# accelerometer_board.net
KiCad netlist of a schematic drawn in EAGLE
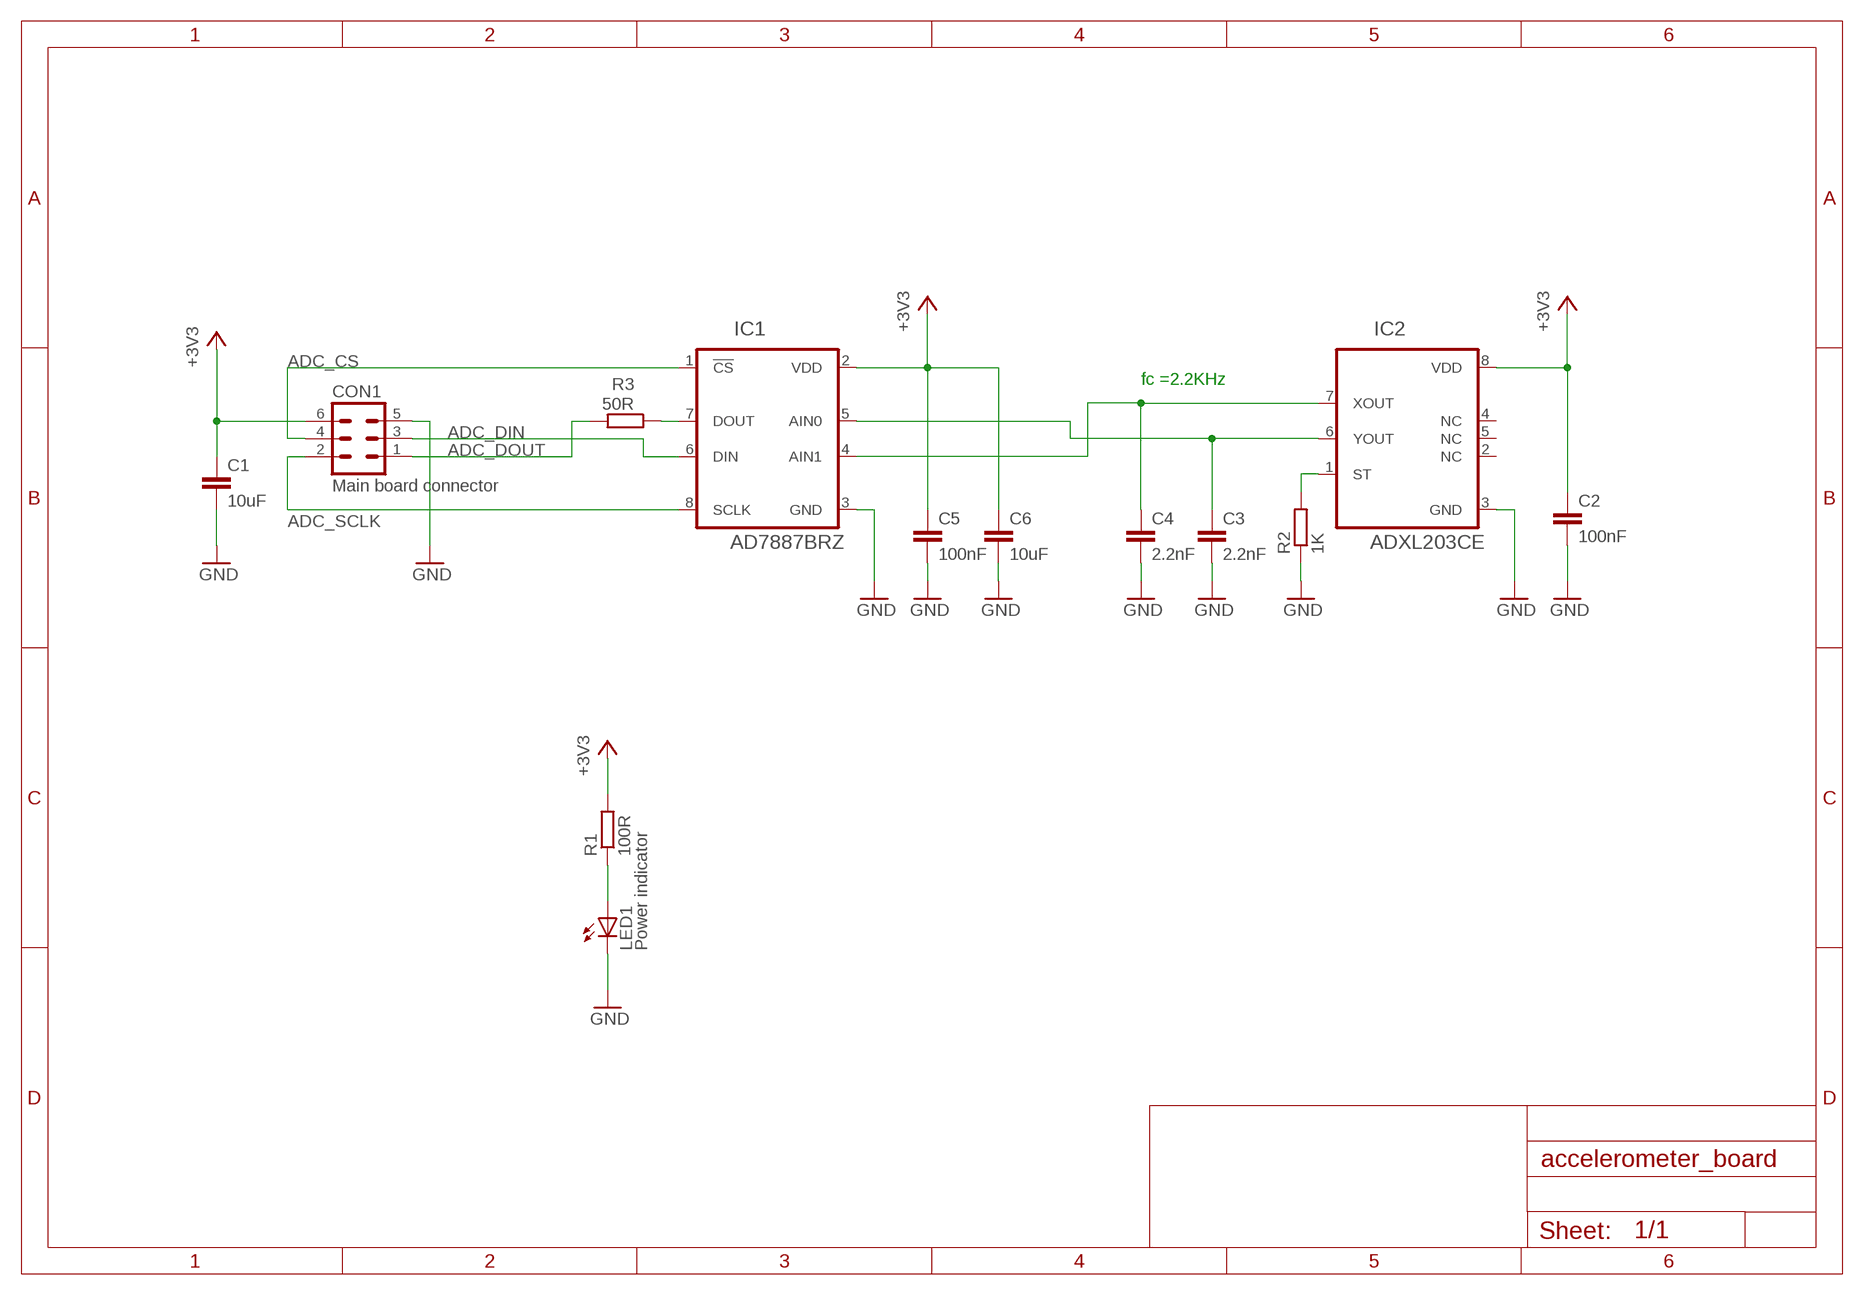
[diagram p0: schematic, sheet 1]

(export (version "E")
  (design (tool "Eeschema 10.0.6"))
  (components
    (comp (ref "C1")
      (value "10uF")
      (footprint "eagle-import:C1206K")
      (libsource (lib "eagle-import") (part "C-EUC1206K"))
    )
    (comp (ref "C2")
      (value "100nF")
      (footprint "eagle-import:C0805K")
      (libsource (lib "eagle-import") (part "C-EUC0805K"))
    )
    (comp (ref "C3")
      (value "2.2nF")
      (footprint "eagle-import:C0805K")
      (libsource (lib "eagle-import") (part "C-EUC0805K"))
    )
    (comp (ref "C4")
      (value "2.2nF")
      (footprint "eagle-import:C0805K")
      (libsource (lib "eagle-import") (part "C-EUC0805K"))
    )
    (comp (ref "C5")
      (value "100nF")
      (footprint "eagle-import:C0805K")
      (libsource (lib "eagle-import") (part "C-EUC0805K"))
    )
    (comp (ref "C6")
      (value "10uF")
      (footprint "eagle-import:C1206K")
      (libsource (lib "eagle-import") (part "C-EUC1206K"))
    )
    (comp (ref "CON1")
      (value "Main board connector")
      (footprint "eagle-import:ML6")
      (libsource (lib "eagle-import") (part "ML6"))
    )
    (comp (ref "IC1")
      (value "AD7887BRZ")
      (footprint "eagle-import:SO08")
      (libsource (lib "eagle-import") (part "AD7887BRZ"))
    )
    (comp (ref "IC2")
      (value "ADXL203CE")
      (footprint "eagle-import:LCC127P500X500X220-8N")
      (fields (field (name "MF") "Analog Devices") (field (name "MP") "ADXL203CE-REEL"))
      (libsource (lib "eagle-import") (part "ADXL203CE"))
    )
    (comp (ref "LED1")
      (value "Power indicator")
      (footprint "eagle-import:CHIP-LED0805")
      (libsource (lib "eagle-import") (part "LEDCHIP-LED0805"))
    )
    (comp (ref "R1")
      (value "100R")
      (footprint "eagle-import:R0805")
      (libsource (lib "eagle-import") (part "R-EU_R0805"))
    )
    (comp (ref "R2")
      (value "1K")
      (footprint "eagle-import:R0805")
      (libsource (lib "eagle-import") (part "R-EU_R0805"))
    )
    (comp (ref "R3")
      (value "50R")
      (footprint "eagle-import:R0805")
      (libsource (lib "eagle-import") (part "R-EU_R0805"))
    )
  )
  (nets
    (net (code "1") (name "+3V3") (class "Default")
      (node (ref "C1") (pin "1") (pinfunction "1_1") (pintype "passive"))
      (node (ref "C2") (pin "1") (pinfunction "1_1") (pintype "passive"))
      (node (ref "C5") (pin "1") (pinfunction "1_1") (pintype "passive"))
      (node (ref "C6") (pin "1") (pinfunction "1_1") (pintype "passive"))
      (node (ref "CON1") (pin "6") (pinfunction "6_6") (pintype "passive"))
      (node (ref "IC1") (pin "2") (pinfunction "VDD_2") (pintype "power_in"))
      (node (ref "IC2") (pin "8") (pinfunction "VDD_8") (pintype "power_in"))
      (node (ref "R1") (pin "2") (pinfunction "2_2") (pintype "passive"))
    )
    (net (code "2") (name "/ADC_CS") (class "Default")
      (node (ref "CON1") (pin "4") (pinfunction "4_4") (pintype "passive"))
      (node (ref "IC1") (pin "1") (pinfunction "~{CS}_1") (pintype "bidirectional"))
    )
    (net (code "3") (name "/ADC_DIN") (class "Default")
      (node (ref "CON1") (pin "3") (pinfunction "3_3") (pintype "passive"))
      (node (ref "IC1") (pin "6") (pinfunction "DIN_6") (pintype "input"))
    )
    (net (code "4") (name "/ADC_DOUT") (class "Default")
      (node (ref "CON1") (pin "1") (pinfunction "1_1") (pintype "passive"))
      (node (ref "R3") (pin "2") (pinfunction "2_2") (pintype "passive"))
    )
    (net (code "5") (name "/ADC_SCLK") (class "Default")
      (node (ref "CON1") (pin "2") (pinfunction "2_2") (pintype "passive"))
      (node (ref "IC1") (pin "8") (pinfunction "SCLK_8") (pintype "input"))
    )
    (net (code "6") (name "GND") (class "Default")
      (node (ref "C1") (pin "2") (pinfunction "2_2") (pintype "passive"))
      (node (ref "C2") (pin "2") (pinfunction "2_2") (pintype "passive"))
      (node (ref "C3") (pin "2") (pinfunction "2_2") (pintype "passive"))
      (node (ref "C4") (pin "2") (pinfunction "2_2") (pintype "passive"))
      (node (ref "C5") (pin "2") (pinfunction "2_2") (pintype "passive"))
      (node (ref "C6") (pin "2") (pinfunction "2_2") (pintype "passive"))
      (node (ref "CON1") (pin "5") (pinfunction "5_5") (pintype "passive"))
      (node (ref "IC1") (pin "3") (pinfunction "GND_3") (pintype "power_in"))
      (node (ref "IC2") (pin "3") (pinfunction "GND_3") (pintype "power_in"))
      (node (ref "LED1") (pin "C") (pinfunction "C_C") (pintype "passive"))
      (node (ref "R2") (pin "1") (pinfunction "1_1") (pintype "passive"))
    )
    (net (code "7") (name "Net-(IC1-AIN0)") (class "Default")
      (node (ref "C3") (pin "1") (pinfunction "1_1") (pintype "passive"))
      (node (ref "IC1") (pin "5") (pinfunction "AIN0_5") (pintype "input"))
      (node (ref "IC2") (pin "6") (pinfunction "YOUT_6") (pintype "output"))
    )
    (net (code "8") (name "Net-(IC1-AIN1)") (class "Default")
      (node (ref "C4") (pin "1") (pinfunction "1_1") (pintype "passive"))
      (node (ref "IC1") (pin "4") (pinfunction "AIN1_4") (pintype "input"))
      (node (ref "IC2") (pin "7") (pinfunction "XOUT_7") (pintype "output"))
    )
    (net (code "9") (name "Net-(IC1-DOUT)") (class "Default")
      (node (ref "IC1") (pin "7") (pinfunction "DOUT_7") (pintype "output"))
      (node (ref "R3") (pin "1") (pinfunction "1_1") (pintype "passive"))
    )
    (net (code "10") (name "Net-(IC2-ST)") (class "Default")
      (node (ref "IC2") (pin "1") (pinfunction "ST_1") (pintype "input"))
      (node (ref "R2") (pin "2") (pinfunction "2_2") (pintype "passive"))
    )
    (net (code "11") (name "Net-(LED1-PadA)") (class "Default")
      (node (ref "LED1") (pin "A") (pinfunction "A_A") (pintype "passive"))
      (node (ref "R1") (pin "1") (pinfunction "1_1") (pintype "passive"))
    )
    (net (code "12") (name "unconnected-(IC2-NC-Pad2)") (class "Default")
      (node (ref "IC2") (pin "2") (pinfunction "NC_2") (pintype "passive"))
    )
    (net (code "13") (name "unconnected-(IC2-NC-Pad4)") (class "Default")
      (node (ref "IC2") (pin "4") (pinfunction "NC_4") (pintype "passive"))
    )
    (net (code "14") (name "unconnected-(IC2-NC-Pad5)") (class "Default")
      (node (ref "IC2") (pin "5") (pinfunction "NC_5") (pintype "passive"))
    )
  )
)
